# Beetech_Metro_Shield_1_0.net
KiCad netlist of a schematic drawn in Altium Designer
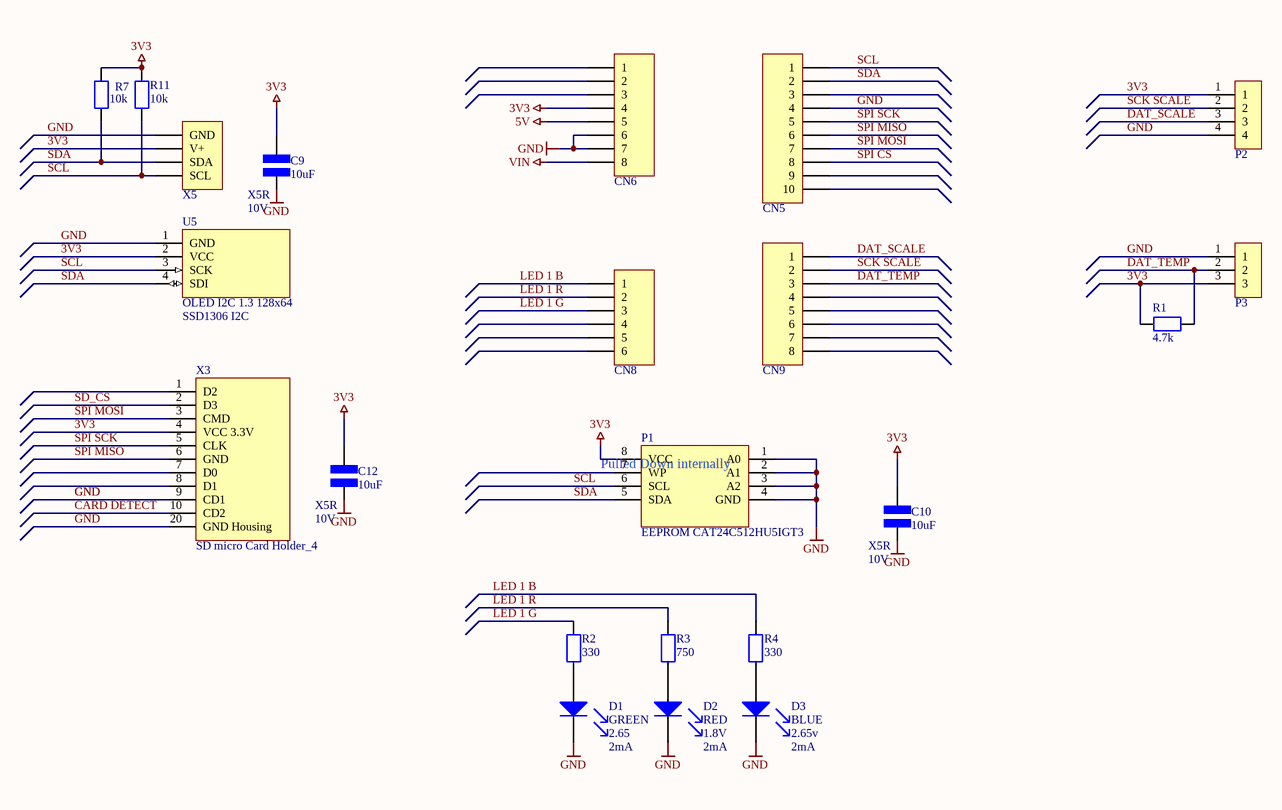
[diagram p0: Beetech Metro Shield 1.0.SchDoc]

(export (version "E")
  (design (tool "Eeschema 10.0.6"))
  (components
    (comp (ref "C9")
      (value "10uF")
      (footprint "CAP 0603 - OUTLINE")
      (description "C CERAMIC SMD")
      (fields
        (field (name "UMAX") "10V")
        (field (name "DIELEKTRIKUM") "X5R")
        (field (name "Comment") "10uF 0603")
      )
      (libsource (lib "Library CAP") (part "10uF 0603"))
    )
    (comp (ref "C10")
      (value "10uF")
      (footprint "CAP 0603 - OUTLINE")
      (description "C CERAMIC SMD")
      (fields
        (field (name "UMAX") "10V")
        (field (name "DIELEKTRIKUM") "X5R")
        (field (name "Comment") "10uF 0603")
      )
      (libsource (lib "Library CAP") (part "10uF 0603"))
    )
    (comp (ref "C12")
      (value "10uF")
      (footprint "CAP 0603 - OUTLINE")
      (description "C CERAMIC SMD")
      (fields
        (field (name "UMAX") "10V")
        (field (name "DIELEKTRIKUM") "X5R")
        (field (name "Comment") "10uF 0603")
      )
      (libsource (lib "Library CAP") (part "10uF 0603"))
    )
    (comp (ref "CN5")
      (value "10-Pin Stiftleiste 10x1 2.54 Low Profile")
      (footprint "10PIN - III")
      (description "Low Profile 10-Pin Stiftleiste 10x1 2.54 Low Profile")
      (libsource (lib "Library Scematic") (part "10-Pin Stiftleiste 10x1 2.54 Low Profile"))
    )
    (comp (ref "CN6")
      (value "8-Pin Stiftleiste 8x1 2.54 Low Profile")
      (footprint "8 PIN - Stiftleiste")
      (description "Low Profile 8-Pin Stiftleiste 8x1 2.54")
      (libsource (lib "Library Scematic") (part "8-Pin Stiftleiste 8x1 2.54 Low Profile"))
    )
    (comp (ref "CN8")
      (value "6-PiN")
      (footprint "6PIN")
      (description "6-Pin")
      (fields (field (name "PUBLISHER") "Altium Limited"))
      (libsource (lib "Library Scematic") (part "6-PiN"))
    )
    (comp (ref "CN9")
      (value "8-Pin Stiftleiste 8x1 2.54 Low Profile")
      (footprint "8 PIN - Stiftleiste")
      (description "Low Profile 8-Pin Stiftleiste 8x1 2.54")
      (libsource (lib "") (part "8-Pin Stiftleiste 8x1 2.54 Low Profile_1"))
    )
    (comp (ref "D1")
      (value "LED Diode SMD LOW CURRENT")
      (footprint "LED SMD 0603 FOOTPRINT")
      (description "LED Green APT1608LZGCK")
      (fields
        (field (name "COLOR") "GREEN")
        (field (name "FORWARD VOLTAGE") "2.65")
        (field (name "IF") "2mA")
      )
      (libsource (lib "Library DIODE") (part "LED Diode SMD - GREEN - 0603 - 2mA_1"))
    )
    (comp (ref "D2")
      (value "LED Diode SMD LOW CURRENT")
      (footprint "LED SMD 0603 FOOTPRINT")
      (description "LED Red APT1608LSECKJ3RV")
      (fields (field (name "COLOR") "RED") (field (name "FORWARD VOLTAGE") "1.8V") (field (name "IF") "2mA"))
      (libsource (lib "Library DIODE") (part "LED Diode SMD - RED - 0603 - 2mA_1"))
    )
    (comp (ref "D3")
      (value "LED Diode SMD LOW CURRENT")
      (footprint "LED SMD 0603 FOOTPRINT")
      (description "LED Blue - APT1608LVBC/D")
      (fields
        (field (name "COLOR") "BLUE")
        (field (name "FORWARD VOLTAGE") "2.65v")
        (field (name "IF") "2mA")
      )
      (libsource (lib "Library DIODE") (part "LED Diode SMD - BLUE - 0603 - 2mA_2"))
    )
    (comp (ref "P1")
      (value "EEPROM CAT24C512HU5IGT3")
      (footprint "UDFN8 3.0x2.0 CAT24C512HU5IGT3")
      (libsource (lib "Library Scematic") (part "EEPROM CAT24C512HU5IGT3"))
    )
    (comp (ref "P2")
      (value "4-Pin Right Angle Housing")
      (footprint "4PIN - RND 205-EK254-2.54-04P")
      (description "4-Pin")
      (libsource (lib "Library Scematic") (part "4-Pin Screw Terminal"))
    )
    (comp (ref "P3")
      (value "3-Pin Right Angle Housing")
      (footprint "3PIN - RND 205-EK254-2.54-03P")
      (description "3-Pin")
      (libsource (lib "Library Scematic") (part "3-Pin Screw Terminal"))
    )
    (comp (ref "R1")
      (value "4.7k")
      (footprint "RES 0603 FOOTPRINT")
      (description "R SMD")
      (fields (field (name "Comment") "4.7k Ohm 0603"))
      (libsource (lib "Library RES") (part "4.7k Ohm 0603"))
    )
    (comp (ref "R2")
      (value "330")
      (footprint "RES 0603 FOOTPRINT - OUTLINE")
      (description "R SMD")
      (fields (field (name "Comment") "330 Ohm 0603"))
      (libsource (lib "Library RES") (part "330 Ohm 0603"))
    )
    (comp (ref "R3")
      (value "750")
      (footprint "RES 0603 FOOTPRINT - OUTLINE")
      (description "R SMD")
      (fields (field (name "Comment") "750 Ohm 0603"))
      (libsource (lib "Library RES") (part "750 Ohm 0603"))
    )
    (comp (ref "R4")
      (value "330")
      (footprint "RES 0603 FOOTPRINT - OUTLINE")
      (description "R SMD")
      (fields (field (name "Comment") "330 Ohm 0603"))
      (libsource (lib "Library RES") (part "330 Ohm 0603"))
    )
    (comp (ref "R7")
      (value "10k")
      (footprint "RES 0603 FOOTPRINT - OUTLINE")
      (description "R SMD")
      (fields (field (name "Comment") "10k Ohm 0603"))
      (libsource (lib "Library RES") (part "10k Ohm 0603"))
    )
    (comp (ref "R11")
      (value "10k")
      (footprint "RES 0603 FOOTPRINT - OUTLINE")
      (description "R SMD")
      (fields (field (name "Comment") "10k Ohm 0603"))
      (libsource (lib "Library RES") (part "10k Ohm 0603"))
    )
    (comp (ref "U5")
      (value "OLED I2C 1.3 128x64")
      (footprint "OLED 1.3 128x64 I2C")
      (description "SSD1306 I2C")
      (fields (field (name "CHIP") "SSD1306 I2C"))
      (libsource (lib "Library Scematic") (part "OLED I2C 1.3 128x64"))
    )
    (comp (ref "X3")
      (value "SD micro Card Holder_4")
      (footprint "SD Card Holder - micro - 4")
      (description "SD micro Card  Holder")
      (libsource (lib "Library Scematic") (part "SD micro Card Holder_4"))
    )
    (comp (ref "X5")
      (value "4-Pin")
      (footprint "QWIIC JST CONNECTOR - SMD 4-PIN")
      (description "QWIIC JST CONNECTOR - SMD 4-PIN")
      (libsource (lib "Library Scematic") (part "4-Pin QWIIC JST CONNECTOR - SMD 4_1"))
    )
  )
  (nets
    (net (code "1") (name "/CARD DETECT") (class "Default")
      (node (ref "X3") (pin "10") (pinfunction "CD2_10") (pintype "passive"))
    )
    (net (code "2") (name "/DAT_SCALE") (class "Default")
      (node (ref "CN9") (pin "1") (pinfunction "1_1") (pintype "passive"))
      (node (ref "P2") (pin "3") (pinfunction "3_3") (pintype "passive"))
    )
    (net (code "3") (name "/DAT_TEMP") (class "Default")
      (node (ref "CN9") (pin "3") (pinfunction "3_3") (pintype "passive"))
      (node (ref "P3") (pin "2") (pinfunction "2_2") (pintype "passive"))
      (node (ref "R1") (pin "1") (pinfunction "1_1") (pintype "passive"))
    )
    (net (code "4") (name "/LED 1 B") (class "Default")
      (node (ref "CN8") (pin "1") (pinfunction "1_1") (pintype "passive"))
      (node (ref "R4") (pin "2") (pinfunction "2_2") (pintype "passive"))
    )
    (net (code "5") (name "/LED 1 G") (class "Default")
      (node (ref "CN8") (pin "3") (pinfunction "3_3") (pintype "passive"))
      (node (ref "R2") (pin "2") (pinfunction "2_2") (pintype "passive"))
    )
    (net (code "6") (name "/LED 1 R") (class "Default")
      (node (ref "CN8") (pin "2") (pinfunction "2_2") (pintype "passive"))
      (node (ref "R3") (pin "2") (pinfunction "2_2") (pintype "passive"))
    )
    (net (code "7") (name "/SCK SCALE") (class "Default")
      (node (ref "CN9") (pin "2") (pinfunction "2_2") (pintype "passive"))
      (node (ref "P2") (pin "2") (pinfunction "2_2") (pintype "passive"))
    )
    (net (code "8") (name "/SCL") (class "Default")
      (node (ref "CN5") (pin "1") (pinfunction "1_1") (pintype "passive"))
      (node (ref "P1") (pin "6") (pinfunction "SCL_6") (pintype "passive"))
      (node (ref "R11") (pin "1") (pinfunction "1_1") (pintype "passive"))
      (node (ref "U5") (pin "3") (pinfunction "SCK_3") (pintype "input"))
      (node (ref "X5") (pin "1") (pinfunction "SCL_1") (pintype "passive"))
    )
    (net (code "9") (name "/SDA") (class "Default")
      (node (ref "CN5") (pin "2") (pinfunction "2_2") (pintype "passive"))
      (node (ref "P1") (pin "5") (pinfunction "SDA_5") (pintype "passive"))
      (node (ref "R7") (pin "1") (pinfunction "1_1") (pintype "passive"))
      (node (ref "U5") (pin "4") (pinfunction "SDI_4") (pintype "bidirectional"))
      (node (ref "X5") (pin "2") (pinfunction "SDA_2") (pintype "passive"))
    )
    (net (code "10") (name "/SD_CS") (class "Default")
      (node (ref "X3") (pin "2") (pinfunction "D3_2") (pintype "passive"))
    )
    (net (code "11") (name "/SPI CS") (class "Default")
      (node (ref "CN5") (pin "8") (pinfunction "8_8") (pintype "passive"))
    )
    (net (code "12") (name "/SPI MISO") (class "Default")
      (node (ref "CN5") (pin "6") (pinfunction "6_6") (pintype "passive"))
      (node (ref "X3") (pin "6") (pinfunction "GND_6") (pintype "passive"))
    )
    (net (code "13") (name "/SPI MOSI") (class "Default")
      (node (ref "CN5") (pin "7") (pinfunction "7_7") (pintype "passive"))
      (node (ref "X3") (pin "3") (pinfunction "CMD_3") (pintype "passive"))
    )
    (net (code "14") (name "/SPI SCK") (class "Default")
      (node (ref "CN5") (pin "5") (pinfunction "5_5") (pintype "passive"))
      (node (ref "X3") (pin "5") (pinfunction "CLK_5") (pintype "passive"))
    )
    (net (code "15") (name "3V3") (class "Default")
      (node (ref "C10") (pin "2") (pinfunction "2_2") (pintype "passive"))
      (node (ref "C12") (pin "2") (pinfunction "2_2") (pintype "passive"))
      (node (ref "C9") (pin "2") (pinfunction "2_2") (pintype "passive"))
      (node (ref "CN6") (pin "4") (pinfunction "4_4") (pintype "passive"))
      (node (ref "P1") (pin "8") (pinfunction "VCC_8") (pintype "passive"))
      (node (ref "P2") (pin "1") (pinfunction "1_1") (pintype "passive"))
      (node (ref "P3") (pin "3") (pinfunction "3_3") (pintype "passive"))
      (node (ref "R1") (pin "2") (pinfunction "2_2") (pintype "passive"))
      (node (ref "R11") (pin "2") (pinfunction "2_2") (pintype "passive"))
      (node (ref "R7") (pin "2") (pinfunction "2_2") (pintype "passive"))
      (node (ref "U5") (pin "2") (pinfunction "VCC_2") (pintype "power_in"))
      (node (ref "X3") (pin "4") (pinfunction "VCC_3.3V_4") (pintype "passive"))
      (node (ref "X5") (pin "3") (pinfunction "V+_3") (pintype "passive"))
    )
    (net (code "16") (name "5V") (class "Default")
      (node (ref "CN6") (pin "5") (pinfunction "5_5") (pintype "passive"))
    )
    (net (code "17") (name "GND") (class "Default")
      (node (ref "C10") (pin "1") (pinfunction "1_1") (pintype "passive"))
      (node (ref "C12") (pin "1") (pinfunction "1_1") (pintype "passive"))
      (node (ref "C9") (pin "1") (pinfunction "1_1") (pintype "passive"))
      (node (ref "CN5") (pin "4") (pinfunction "4_4") (pintype "passive"))
      (node (ref "CN6") (pin "6") (pinfunction "6_6") (pintype "passive"))
      (node (ref "CN6") (pin "7") (pinfunction "7_7") (pintype "passive"))
      (node (ref "D1") (pin "2") (pinfunction "K_2") (pintype "passive"))
      (node (ref "D2") (pin "2") (pinfunction "K_2") (pintype "passive"))
      (node (ref "D3") (pin "2") (pinfunction "K_2") (pintype "passive"))
      (node (ref "P1") (pin "1") (pinfunction "A0_1") (pintype "passive"))
      (node (ref "P1") (pin "2") (pinfunction "A1_2") (pintype "passive"))
      (node (ref "P1") (pin "3") (pinfunction "A2_3") (pintype "passive"))
      (node (ref "P1") (pin "4") (pinfunction "GND_4") (pintype "passive"))
      (node (ref "P2") (pin "4") (pinfunction "4_4") (pintype "passive"))
      (node (ref "P3") (pin "1") (pinfunction "1_1") (pintype "passive"))
      (node (ref "U5") (pin "1") (pinfunction "GND_1") (pintype "power_in"))
      (node (ref "X3") (pin "20") (pinfunction "GND_Housing_20") (pintype "passive"))
      (node (ref "X3") (pin "9") (pinfunction "CD1_9") (pintype "passive"))
      (node (ref "X5") (pin "4") (pinfunction "GND_4") (pintype "passive"))
    )
    (net (code "18") (name "Net-(D1-A)") (class "Default")
      (node (ref "D1") (pin "1") (pinfunction "A_1") (pintype "passive"))
      (node (ref "R2") (pin "1") (pinfunction "1_1") (pintype "passive"))
    )
    (net (code "19") (name "Net-(D2-A)") (class "Default")
      (node (ref "D2") (pin "1") (pinfunction "A_1") (pintype "passive"))
      (node (ref "R3") (pin "1") (pinfunction "1_1") (pintype "passive"))
    )
    (net (code "20") (name "Net-(D3-A)") (class "Default")
      (node (ref "D3") (pin "1") (pinfunction "A_1") (pintype "passive"))
      (node (ref "R4") (pin "1") (pinfunction "1_1") (pintype "passive"))
    )
    (net (code "21") (name "VIN") (class "Default")
      (node (ref "CN6") (pin "8") (pinfunction "8_8") (pintype "passive"))
    )
    (net (code "22") (name "unconnected-(CN5-Pad3)") (class "Default")
      (node (ref "CN5") (pin "3") (pinfunction "3_3") (pintype "passive"))
    )
    (net (code "23") (name "unconnected-(CN5-Pad9)") (class "Default")
      (node (ref "CN5") (pin "9") (pinfunction "9_9") (pintype "passive"))
    )
    (net (code "24") (name "unconnected-(CN5-Pad10)") (class "Default")
      (node (ref "CN5") (pin "10") (pinfunction "10_10") (pintype "passive"))
    )
    (net (code "25") (name "unconnected-(CN6-Pad1)") (class "Default")
      (node (ref "CN6") (pin "1") (pinfunction "1_1") (pintype "passive"))
    )
    (net (code "26") (name "unconnected-(CN6-Pad2)") (class "Default")
      (node (ref "CN6") (pin "2") (pinfunction "2_2") (pintype "passive"))
    )
    (net (code "27") (name "unconnected-(CN6-Pad3)") (class "Default")
      (node (ref "CN6") (pin "3") (pinfunction "3_3") (pintype "passive"))
    )
    (net (code "28") (name "unconnected-(CN8-Pad4)") (class "Default")
      (node (ref "CN8") (pin "4") (pinfunction "4_4") (pintype "passive"))
    )
    (net (code "29") (name "unconnected-(CN8-Pad5)") (class "Default")
      (node (ref "CN8") (pin "5") (pinfunction "5_5") (pintype "passive"))
    )
    (net (code "30") (name "unconnected-(CN8-Pad6)") (class "Default")
      (node (ref "CN8") (pin "6") (pinfunction "6_6") (pintype "passive"))
    )
    (net (code "31") (name "unconnected-(CN9-Pad4)") (class "Default")
      (node (ref "CN9") (pin "4") (pinfunction "4_4") (pintype "passive"))
    )
    (net (code "32") (name "unconnected-(CN9-Pad5)") (class "Default")
      (node (ref "CN9") (pin "5") (pinfunction "5_5") (pintype "passive"))
    )
    (net (code "33") (name "unconnected-(CN9-Pad6)") (class "Default")
      (node (ref "CN9") (pin "6") (pinfunction "6_6") (pintype "passive"))
    )
    (net (code "34") (name "unconnected-(CN9-Pad7)") (class "Default")
      (node (ref "CN9") (pin "7") (pinfunction "7_7") (pintype "passive"))
    )
    (net (code "35") (name "unconnected-(CN9-Pad8)") (class "Default")
      (node (ref "CN9") (pin "8") (pinfunction "8_8") (pintype "passive"))
    )
    (net (code "36") (name "unconnected-(P1-WP-Pad7)") (class "Default")
      (node (ref "P1") (pin "7") (pinfunction "WP_7") (pintype "passive"))
    )
    (net (code "37") (name "unconnected-(X3-D0-Pad7)") (class "Default")
      (node (ref "X3") (pin "7") (pinfunction "D0_7") (pintype "passive"))
    )
    (net (code "38") (name "unconnected-(X3-D1-Pad8)") (class "Default")
      (node (ref "X3") (pin "8") (pinfunction "D1_8") (pintype "passive"))
    )
    (net (code "39") (name "unconnected-(X3-D2-Pad1)") (class "Default")
      (node (ref "X3") (pin "1") (pinfunction "D2_1") (pintype "passive"))
    )
  )
)
